# TelTail_Lights_SP_4v1.net
KiCad netlist of a schematic drawn in EAGLE
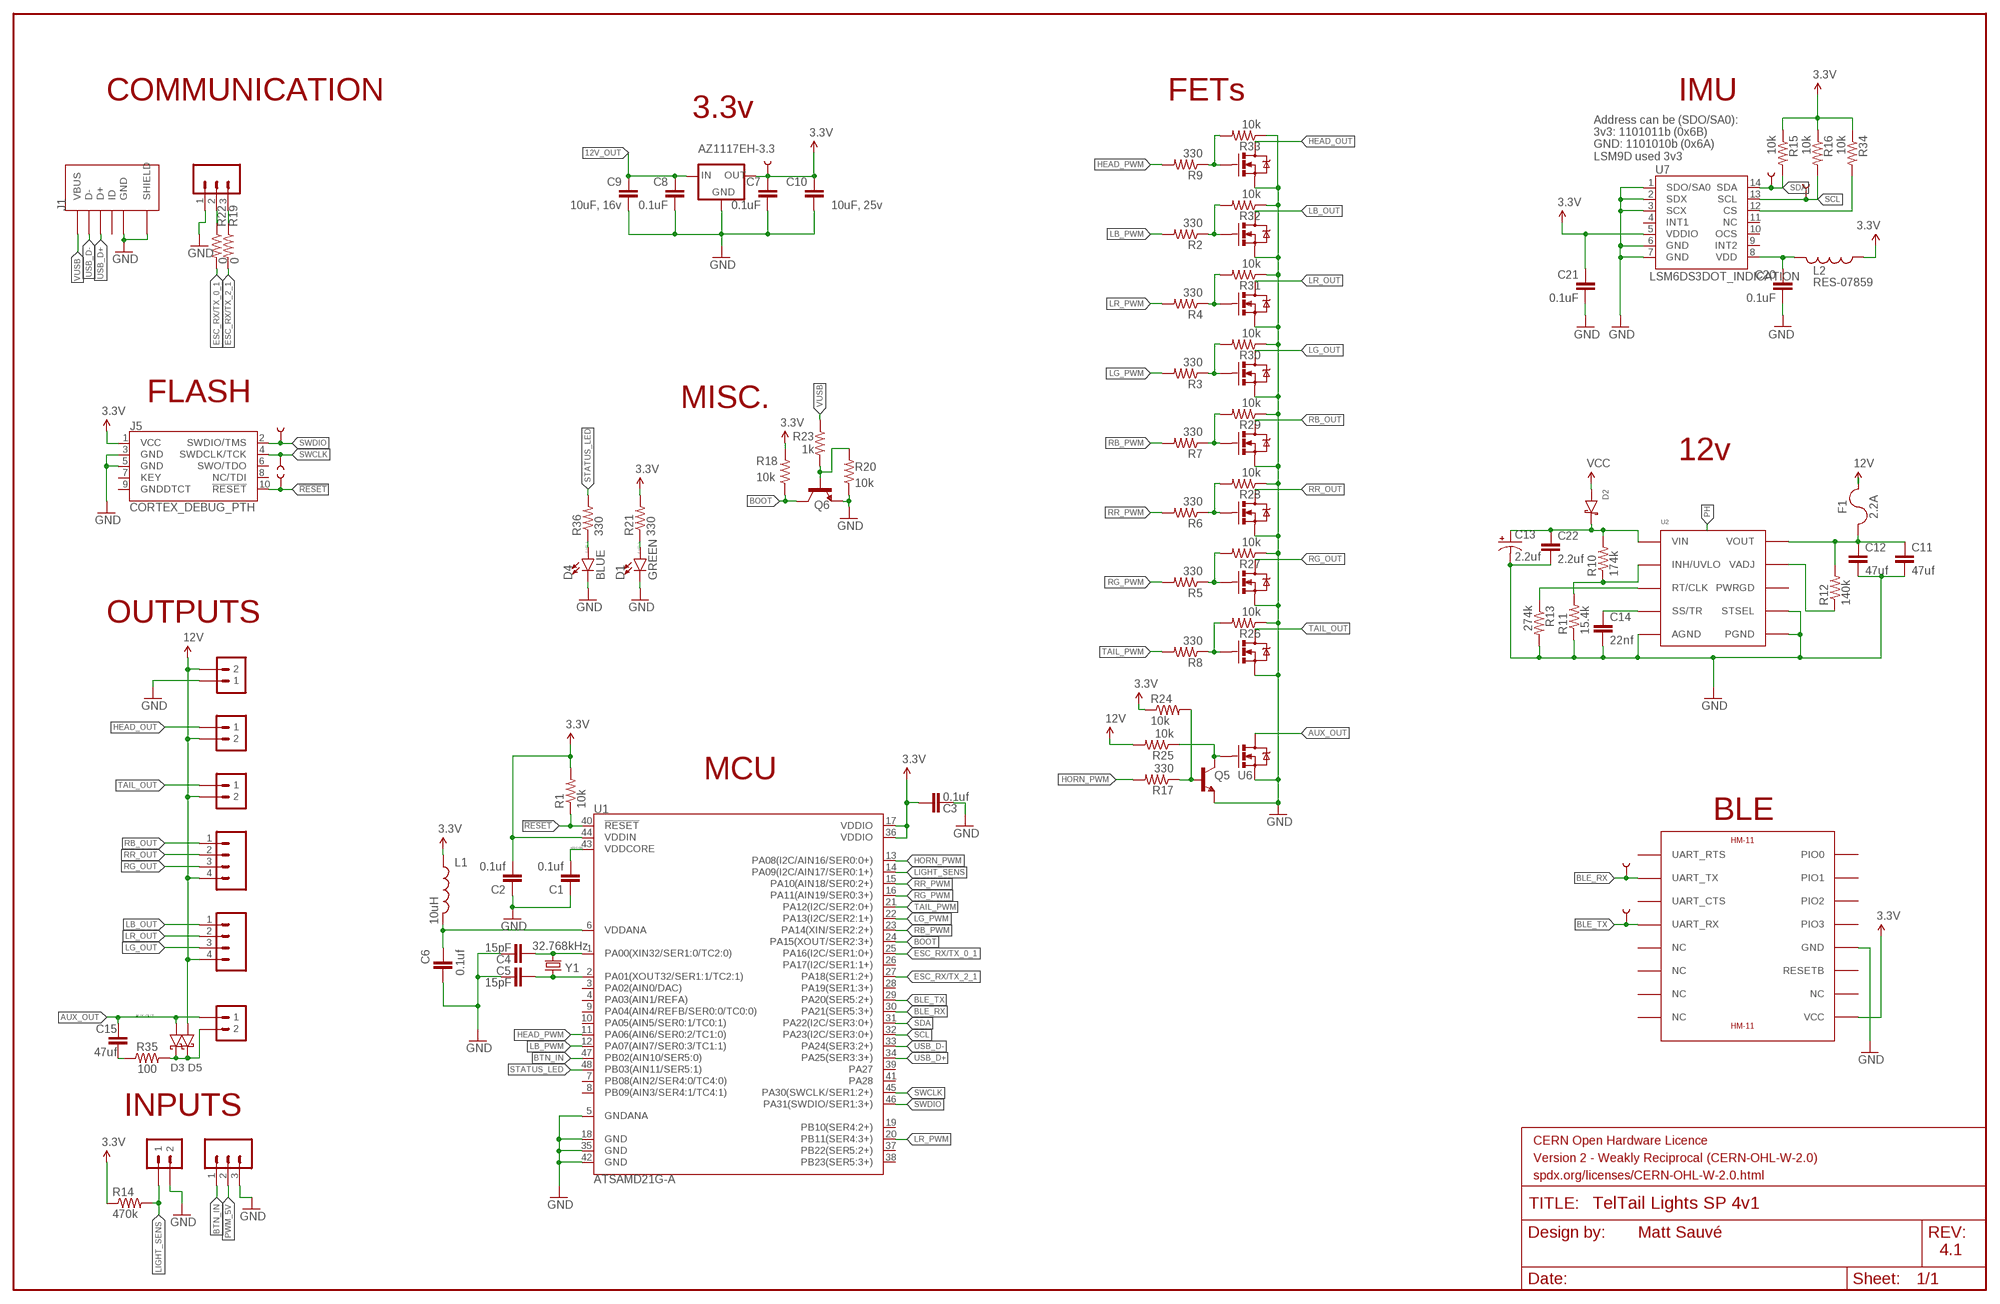
[diagram p0: schematic, sheet 1]

(export (version "E")
  (design (tool "Eeschema 10.0.6"))
  (components
    (comp (ref "C1")
      (value "0.1uf")
      (footprint "eagle-import:0603-CAP")
      (libsource (lib "eagle-import") (part "CAP0603-CAP"))
    )
    (comp (ref "C2")
      (value "0.1uf")
      (footprint "eagle-import:0603-CAP")
      (libsource (lib "eagle-import") (part "CAP0603-CAP"))
    )
    (comp (ref "C3")
      (value "0.1uf")
      (footprint "eagle-import:0603-CAP")
      (libsource (lib "eagle-import") (part "CAP0603-CAP"))
    )
    (comp (ref "C4")
      (value "15pF")
      (footprint "eagle-import:0603-CAP")
      (libsource (lib "eagle-import") (part "CAP0603-CAP"))
    )
    (comp (ref "C5")
      (value "15pF")
      (footprint "eagle-import:0603-CAP")
      (libsource (lib "eagle-import") (part "CAP0603-CAP"))
    )
    (comp (ref "C6")
      (value "0.1uf")
      (footprint "eagle-import:0603-CAP")
      (libsource (lib "eagle-import") (part "CAP0603-CAP"))
    )
    (comp (ref "C7")
      (value "0.1uF")
      (footprint "eagle-import:0603-CAP")
      (libsource (lib "eagle-import") (part "CAP0603-CAP"))
    )
    (comp (ref "C8")
      (value "0.1uF")
      (footprint "eagle-import:0603-CAP")
      (libsource (lib "eagle-import") (part "CAP0603-CAP"))
    )
    (comp (ref "C9")
      (value "10uF, 16v")
      (footprint "eagle-import:0603-CAP")
      (libsource (lib "eagle-import") (part "CAP0603-CAP"))
    )
    (comp (ref "C10")
      (value "10uF, 25v")
      (footprint "eagle-import:0603-CAP")
      (libsource (lib "eagle-import") (part "CAP0603-CAP"))
    )
    (comp (ref "C11")
      (value "47uf")
      (footprint "eagle-import:1210-CAP")
      (libsource (lib "eagle-import") (part "CAP1210"))
    )
    (comp (ref "C12")
      (value "47uf")
      (footprint "eagle-import:1210-CAP")
      (libsource (lib "eagle-import") (part "CAP1210"))
    )
    (comp (ref "C13")
      (value "2.2uf")
      (footprint "eagle-import:PANASONIC_B")
      (libsource (lib "eagle-import") (part "CPOL-USB"))
    )
    (comp (ref "C14")
      (value "22nf")
      (footprint "eagle-import:0402-CAP")
      (libsource (lib "eagle-import") (part "CAP0402-CAP"))
    )
    (comp (ref "C15")
      (value "47uf")
      (footprint "eagle-import:1210-CAP")
      (libsource (lib "eagle-import") (part "CAP1210"))
    )
    (comp (ref "C20")
      (value "0.1uF")
      (footprint "eagle-import:0603-CAP")
      (libsource (lib "eagle-import") (part "CAP0603-CAP"))
    )
    (comp (ref "C21")
      (value "0.1uF")
      (footprint "eagle-import:0603-CAP")
      (libsource (lib "eagle-import") (part "CAP0603-CAP"))
    )
    (comp (ref "C22")
      (value "2.2uf")
      (footprint "eagle-import:1210-CAP")
      (libsource (lib "eagle-import") (part "CAP1210"))
    )
    (comp (ref "D1")
      (value "GREEN")
      (footprint "eagle-import:LED-0603-2")
      (libsource (lib "eagle-import") (part "LED0603"))
    )
    (comp (ref "D2")
      (value "SS210ATR")
      (footprint "eagle-import:DO-214AC")
      (libsource (lib "eagle-import") (part "SS210ATR"))
    )
    (comp (ref "D3")
      (value "PMEG2010ER")
      (footprint "eagle-import:SOD-123W")
      (libsource (lib "eagle-import") (part "PMEG2010ER"))
    )
    (comp (ref "D4")
      (value "BLUE")
      (footprint "eagle-import:LED-0603-2")
      (libsource (lib "eagle-import") (part "LED0603"))
    )
    (comp (ref "D5")
      (value "PMEG2010ER")
      (footprint "eagle-import:SOD-123W")
      (libsource (lib "eagle-import") (part "PMEG2010ER"))
    )
    (comp (ref "F1")
      (value "2.2A")
      (footprint "eagle-import:1206-FUSE")
      (libsource (lib "eagle-import") (part "FUSE-1206"))
    )
    (comp (ref "FRAME2")
      (value "FRAME-LEDGER_CERN_WEAK")
      (footprint "eagle-import:CERN_WEAK")
      (libsource (lib "eagle-import") (part "FRAME-LEDGER_CERN_WEAK"))
    )
    (comp (ref "J1")
      (value "USB3160-XX-XXXX-X-X_REVA")
      (footprint "eagle-import:GCT_USB3160-XX-XXXX-X-X_REVA")
      (fields (field (name "MF") "Global Connector Technology") (field (name "MP") "USB3160-30-0170-0-C"))
      (libsource (lib "eagle-import") (part "USB3160-XX-XXXX-X-X_REVA"))
    )
    (comp (ref "J3")
      (value "JST_PH_3POS")
      (footprint "eagle-import:JST_PH_3POS")
      (libsource (lib "eagle-import") (part "JST_PH_3POS"))
    )
    (comp (ref "J4")
      (value "JST_PH_2POS")
      (footprint "eagle-import:JST_PH_2POS")
      (libsource (lib "eagle-import") (part "JST_PH_2POS"))
    )
    (comp (ref "J5")
      (value "CORTEX_DEBUG_PTH")
      (footprint "eagle-import:2X5-PTH-1.27MM-2")
      (libsource (lib "eagle-import") (part "CORTEX_DEBUG_PTH"))
    )
    (comp (ref "J6")
      (value "JST_PH_2POS")
      (footprint "eagle-import:JST_PH_2POS")
      (libsource (lib "eagle-import") (part "JST_PH_2POS"))
    )
    (comp (ref "J7")
      (value "JST_PH_2POS")
      (footprint "eagle-import:JST_PH_2POS")
      (libsource (lib "eagle-import") (part "JST_PH_2POS"))
    )
    (comp (ref "J8")
      (value "JST_PH_4POS")
      (footprint "eagle-import:JST_PH_4POS")
      (libsource (lib "eagle-import") (part "JST_PH_4POS"))
    )
    (comp (ref "J9")
      (value "JST_PH_4POS")
      (footprint "eagle-import:JST_PH_4POS")
      (libsource (lib "eagle-import") (part "JST_PH_4POS"))
    )
    (comp (ref "J10")
      (value "JST_PH_2POS")
      (footprint "eagle-import:JST_PH_2POS")
      (libsource (lib "eagle-import") (part "JST_PH_2POS"))
    )
    (comp (ref "J11")
      (value "JST_PH_2POS")
      (footprint "eagle-import:JST_PH_2POS")
      (libsource (lib "eagle-import") (part "JST_PH_2POS"))
    )
    (comp (ref "J12")
      (value "JST_PH_3POS")
      (footprint "eagle-import:JST_PH_3POS")
      (libsource (lib "eagle-import") (part "JST_PH_3POS"))
    )
    (comp (ref "L1")
      (value "10uH")
      (footprint "eagle-import:0603-IND")
      (libsource (lib "eagle-import") (part "INDUCTOR0603"))
    )
    (comp (ref "L2")
      (value "RES-07859")
      (footprint "eagle-import:0603-IND")
      (libsource (lib "eagle-import") (part "INDUCTOR0603"))
    )
    (comp (ref "Q1")
      (value "DUAL_NFET_3.5A")
      (footprint "eagle-import:TSOT26")
      (libsource (lib "eagle-import") (part "DUAL_NFET_3.5A"))
    )
    (comp (ref "Q2")
      (value "DUAL_NFET_3.5A")
      (footprint "eagle-import:TSOT26")
      (libsource (lib "eagle-import") (part "DUAL_NFET_3.5A"))
    )
    (comp (ref "Q3")
      (value "DUAL_NFET_3.5A")
      (footprint "eagle-import:TSOT26")
      (libsource (lib "eagle-import") (part "DUAL_NFET_3.5A"))
    )
    (comp (ref "Q4")
      (value "DUAL_NFET_3.5A")
      (footprint "eagle-import:TSOT26")
      (libsource (lib "eagle-import") (part "DUAL_NFET_3.5A"))
    )
    (comp (ref "Q5")
      (value "500mA/300V")
      (footprint "eagle-import:SOT23-3")
      (libsource (lib "eagle-import") (part "TRANS_NPN-MMBTA42"))
    )
    (comp (ref "Q6")
      (value "500mA/300V")
      (footprint "eagle-import:SOT23-3")
      (libsource (lib "eagle-import") (part "TRANS_NPN-MMBTA42"))
    )
    (comp (ref "R1")
      (value "10k")
      (footprint "eagle-import:RES-0402")
      (libsource (lib "eagle-import") (part "RES-0402"))
    )
    (comp (ref "R2")
      (value "330")
      (footprint "eagle-import:RES-0402")
      (libsource (lib "eagle-import") (part "RES-0402"))
    )
    (comp (ref "R3")
      (value "330")
      (footprint "eagle-import:RES-0402")
      (libsource (lib "eagle-import") (part "RES-0402"))
    )
    (comp (ref "R4")
      (value "330")
      (footprint "eagle-import:RES-0402")
      (libsource (lib "eagle-import") (part "RES-0402"))
    )
    (comp (ref "R5")
      (value "330")
      (footprint "eagle-import:RES-0402")
      (libsource (lib "eagle-import") (part "RES-0402"))
    )
    (comp (ref "R6")
      (value "330")
      (footprint "eagle-import:RES-0402")
      (libsource (lib "eagle-import") (part "RES-0402"))
    )
    (comp (ref "R7")
      (value "330")
      (footprint "eagle-import:RES-0402")
      (libsource (lib "eagle-import") (part "RES-0402"))
    )
    (comp (ref "R8")
      (value "330")
      (footprint "eagle-import:RES-0402")
      (libsource (lib "eagle-import") (part "RES-0402"))
    )
    (comp (ref "R9")
      (value "330")
      (footprint "eagle-import:RES-0402")
      (libsource (lib "eagle-import") (part "RES-0402"))
    )
    (comp (ref "R10")
      (value "174k")
      (footprint "eagle-import:RES-0402")
      (libsource (lib "eagle-import") (part "RES-0402"))
    )
    (comp (ref "R11")
      (value "15.4k")
      (footprint "eagle-import:RES-0402")
      (libsource (lib "eagle-import") (part "RES-0402"))
    )
    (comp (ref "R12")
      (value "140k")
      (footprint "eagle-import:RES-0402")
      (libsource (lib "eagle-import") (part "RES-0402"))
    )
    (comp (ref "R13")
      (value "274k")
      (footprint "eagle-import:RES-0402")
      (libsource (lib "eagle-import") (part "RES-0402"))
    )
    (comp (ref "R14")
      (value "470k")
      (footprint "eagle-import:RES-0603")
      (libsource (lib "eagle-import") (part "RES-0603"))
    )
    (comp (ref "R15")
      (value "10k")
      (footprint "eagle-import:RES-0402")
      (libsource (lib "eagle-import") (part "RES-0402"))
    )
    (comp (ref "R16")
      (value "10k")
      (footprint "eagle-import:RES-0402")
      (libsource (lib "eagle-import") (part "RES-0402"))
    )
    (comp (ref "R17")
      (value "330")
      (footprint "eagle-import:RES-0402")
      (libsource (lib "eagle-import") (part "RES-0402"))
    )
    (comp (ref "R18")
      (value "10k")
      (footprint "eagle-import:RES-0402")
      (libsource (lib "eagle-import") (part "RES-0402"))
    )
    (comp (ref "R19")
      (value "0")
      (footprint "eagle-import:RES-0603")
      (libsource (lib "eagle-import") (part "RES-0603"))
    )
    (comp (ref "R20")
      (value "10k")
      (footprint "eagle-import:RES-0402")
      (libsource (lib "eagle-import") (part "RES-0402"))
    )
    (comp (ref "R21")
      (value "330")
      (footprint "eagle-import:RES-0402")
      (libsource (lib "eagle-import") (part "RES-0402"))
    )
    (comp (ref "R22")
      (value "0")
      (footprint "eagle-import:RES-0603")
      (libsource (lib "eagle-import") (part "RES-0603"))
    )
    (comp (ref "R23")
      (value "1k")
      (footprint "eagle-import:RES-0402")
      (libsource (lib "eagle-import") (part "RES-0402"))
    )
    (comp (ref "R24")
      (value "10k")
      (footprint "eagle-import:RES-0402")
      (libsource (lib "eagle-import") (part "RES-0402"))
    )
    (comp (ref "R25")
      (value "10k")
      (footprint "eagle-import:RES-0402")
      (libsource (lib "eagle-import") (part "RES-0402"))
    )
    (comp (ref "R26")
      (value "10k")
      (footprint "eagle-import:RES-0402")
      (libsource (lib "eagle-import") (part "RES-0402"))
    )
    (comp (ref "R27")
      (value "10k")
      (footprint "eagle-import:RES-0402")
      (libsource (lib "eagle-import") (part "RES-0402"))
    )
    (comp (ref "R28")
      (value "10k")
      (footprint "eagle-import:RES-0402")
      (libsource (lib "eagle-import") (part "RES-0402"))
    )
    (comp (ref "R29")
      (value "10k")
      (footprint "eagle-import:RES-0402")
      (libsource (lib "eagle-import") (part "RES-0402"))
    )
    (comp (ref "R30")
      (value "10k")
      (footprint "eagle-import:RES-0402")
      (libsource (lib "eagle-import") (part "RES-0402"))
    )
    (comp (ref "R31")
      (value "10k")
      (footprint "eagle-import:RES-0402")
      (libsource (lib "eagle-import") (part "RES-0402"))
    )
    (comp (ref "R32")
      (value "10k")
      (footprint "eagle-import:RES-0402")
      (libsource (lib "eagle-import") (part "RES-0402"))
    )
    (comp (ref "R33")
      (value "10k")
      (footprint "eagle-import:RES-0402")
      (libsource (lib "eagle-import") (part "RES-0402"))
    )
    (comp (ref "R34")
      (value "10k")
      (footprint "eagle-import:RES-0402")
      (libsource (lib "eagle-import") (part "RES-0402"))
    )
    (comp (ref "R35")
      (value "100")
      (footprint "eagle-import:0805-RES")
      (libsource (lib "eagle-import") (part "RESISTOR0805"))
    )
    (comp (ref "R36")
      (value "330")
      (footprint "eagle-import:RES-0402")
      (libsource (lib "eagle-import") (part "RES-0402"))
    )
    (comp (ref "TP1")
      (value "1MM_TP")
      (footprint "eagle-import:1MM_TP")
      (libsource (lib "eagle-import") (part "1MM_TP"))
    )
    (comp (ref "TP2")
      (value "1MM_TP")
      (footprint "eagle-import:1MM_TP")
      (libsource (lib "eagle-import") (part "1MM_TP"))
    )
    (comp (ref "TP3")
      (value "1MM_TP")
      (footprint "eagle-import:1MM_TP")
      (libsource (lib "eagle-import") (part "1MM_TP"))
    )
    (comp (ref "TP4")
      (value "1MM_TP")
      (footprint "eagle-import:1MM_TP")
      (libsource (lib "eagle-import") (part "1MM_TP"))
    )
    (comp (ref "TP5")
      (value "1MM_TP")
      (footprint "eagle-import:1MM_TP")
      (libsource (lib "eagle-import") (part "1MM_TP"))
    )
    (comp (ref "TP8")
      (value "1MM_TP")
      (footprint "eagle-import:1MM_TP")
      (libsource (lib "eagle-import") (part "1MM_TP"))
    )
    (comp (ref "TP9")
      (value "1MM_TP")
      (footprint "eagle-import:1MM_TP")
      (libsource (lib "eagle-import") (part "1MM_TP"))
    )
    (comp (ref "TP10")
      (value "1MM_TP")
      (footprint "eagle-import:1MM_TP")
      (libsource (lib "eagle-import") (part "1MM_TP"))
    )
    (comp (ref "U1")
      (value "ATSAMD21G-A")
      (footprint "eagle-import:TQFP-48")
      (libsource (lib "eagle-import") (part "ATSAMD21G-A"))
    )
    (comp (ref "U2")
      (value "LMZ35003")
      (footprint "eagle-import:41-BQFN")
      (libsource (lib "eagle-import") (part "LMZ35003"))
    )
    (comp (ref "U3")
      (value "HM-11")
      (footprint "eagle-import:HM-11")
      (libsource (lib "eagle-import") (part "HM-11"))
    )
    (comp (ref "U4")
      (value "AZ1117EH-3.3")
      (footprint "eagle-import:SOT-223")
      (libsource (lib "eagle-import") (part "AZ1117EH-3.3"))
    )
    (comp (ref "U6")
      (value "PSMN8R5-60YS")
      (footprint "eagle-import:SOT669")
      (libsource (lib "eagle-import") (part "PSMN8R5-60YS"))
    )
    (comp (ref "U7")
      (value "LSM6DS3DOT_INDICATION")
      (footprint "eagle-import:LGA14L_DOT_INDICATOR")
      (libsource (lib "eagle-import") (part "LSM6DS3DOT_INDICATION"))
    )
    (comp (ref "Y1")
      (value "32.768kHz")
      (footprint "eagle-import:CRYSTAL-SMD-3.2X1.5MM")
      (libsource (lib "eagle-import") (part "CRYSTAL-32.768KHZSMD-3.2X1.5"))
    )
  )
  (nets
    (net (code "1") (name "/P_LED_0") (class "Default")
      (node (ref "D1") (pin "A") (pinfunction "A_A") (pintype "passive"))
      (node (ref "R21") (pin "1") (pinfunction "1_1") (pintype "passive"))
    )
    (net (code "2") (name "/S_LED_0") (class "Default")
      (node (ref "D4") (pin "A") (pinfunction "A_A") (pintype "passive"))
      (node (ref "R36") (pin "1") (pinfunction "1_1") (pintype "passive"))
    )
    (net (code "3") (name "/VDDCORE") (class "Default")
      (node (ref "C1") (pin "2") (pinfunction "2_2") (pintype "passive"))
      (node (ref "U1") (pin "43") (pinfunction "VDDCORE_43") (pintype "bidirectional"))
    )
    (net (code "4") (name "/~{RESET}") (class "Default")
      (node (ref "J5") (pin "10") (pinfunction "~{RESET}_10") (pintype "bidirectional"))
      (node (ref "R1") (pin "1") (pinfunction "1_1") (pintype "passive"))
      (node (ref "TP10") (pin "P$1") (pinfunction "1_P$1") (pintype "bidirectional"))
      (node (ref "U1") (pin "40") (pinfunction "~{RESET}_40") (pintype "bidirectional"))
    )
    (net (code "5") (name "3.3V") (class "Default")
      (node (ref "C10") (pin "1") (pinfunction "1_1") (pintype "passive"))
      (node (ref "C2") (pin "2") (pinfunction "2_2") (pintype "passive"))
      (node (ref "C21") (pin "1") (pinfunction "1_1") (pintype "passive"))
      (node (ref "C3") (pin "2") (pinfunction "2_2") (pintype "passive"))
      (node (ref "C7") (pin "1") (pinfunction "1_1") (pintype "passive"))
      (node (ref "J5") (pin "1") (pinfunction "VCC_1") (pintype "bidirectional"))
      (node (ref "L1") (pin "1") (pinfunction "1_1") (pintype "passive"))
      (node (ref "L2") (pin "1") (pinfunction "1_1") (pintype "passive"))
      (node (ref "R1") (pin "2") (pinfunction "2_2") (pintype "passive"))
      (node (ref "R14") (pin "1") (pinfunction "1_1") (pintype "passive"))
      (node (ref "R15") (pin "1") (pinfunction "1_1") (pintype "passive"))
      (node (ref "R16") (pin "1") (pinfunction "1_1") (pintype "passive"))
      (node (ref "R18") (pin "2") (pinfunction "2_2") (pintype "passive"))
      (node (ref "R21") (pin "2") (pinfunction "2_2") (pintype "passive"))
      (node (ref "R24") (pin "1") (pinfunction "1_1") (pintype "passive"))
      (node (ref "R34") (pin "1") (pinfunction "1_1") (pintype "passive"))
      (node (ref "TP3") (pin "P$1") (pinfunction "1_P$1") (pintype "bidirectional"))
      (node (ref "U1") (pin "17") (pinfunction "VDDIO_17") (pintype "bidirectional"))
      (node (ref "U1") (pin "36") (pinfunction "VDDIO_36") (pintype "bidirectional"))
      (node (ref "U1") (pin "44") (pinfunction "VDDIN_44") (pintype "bidirectional"))
      (node (ref "U3") (pin "VCC") (pinfunction "VCC_VCC") (pintype "bidirectional"))
      (node (ref "U4") (pin "2") (pinfunction "OUT_2") (pintype "passive"))
      (node (ref "U4") (pin "4") (pinfunction "OUT_4") (pintype "passive"))
      (node (ref "U7") (pin "5") (pinfunction "VDDIO_5") (pintype "bidirectional"))
    )
    (net (code "6") (name "12V") (class "Default")
      (node (ref "D5") (pin "2") (pinfunction "ANODE_2") (pintype "bidirectional"))
      (node (ref "F1") (pin "2") (pinfunction "2_2") (pintype "bidirectional"))
      (node (ref "J4") (pin "2") (pinfunction "2_2") (pintype "passive"))
      (node (ref "J6") (pin "2") (pinfunction "2_2") (pintype "passive"))
      (node (ref "J7") (pin "2") (pinfunction "2_2") (pintype "passive"))
      (node (ref "J8") (pin "4") (pinfunction "4_4") (pintype "passive"))
      (node (ref "J9") (pin "4") (pinfunction "4_4") (pintype "passive"))
      (node (ref "R25") (pin "2") (pinfunction "2_2") (pintype "passive"))
    )
    (net (code "7") (name "12V_OUT") (class "Default")
      (node (ref "C11") (pin "1") (pinfunction "1_1") (pintype "passive"))
      (node (ref "C12") (pin "1") (pinfunction "1_1") (pintype "passive"))
      (node (ref "C8") (pin "1") (pinfunction "1_1") (pintype "passive"))
      (node (ref "C9") (pin "1") (pinfunction "1_1") (pintype "passive"))
      (node (ref "F1") (pin "1") (pinfunction "1_1") (pintype "bidirectional"))
      (node (ref "R12") (pin "2") (pinfunction "2_2") (pintype "passive"))
      (node (ref "U2") (pin "P$10") (pinfunction "VOUT_P$10") (pintype "bidirectional"))
      (node (ref "U2") (pin "P$11") (pinfunction "VOUT_P$11") (pintype "bidirectional"))
      (node (ref "U2") (pin "P$12") (pinfunction "VOUT_P$12") (pintype "bidirectional"))
      (node (ref "U2") (pin "P$13") (pinfunction "VOUT_P$13") (pintype "bidirectional"))
      (node (ref "U2") (pin "P$14") (pinfunction "VOUT_P$14") (pintype "bidirectional"))
      (node (ref "U2") (pin "P$15") (pinfunction "VOUT_P$15") (pintype "bidirectional"))
      (node (ref "U2") (pin "VOUT") (pinfunction "VOUT_VOUT") (pintype "bidirectional"))
      (node (ref "U4") (pin "3") (pinfunction "IN_3") (pintype "input"))
    )
    (net (code "8") (name "AUX_OUT") (class "Default")
      (node (ref "C15") (pin "1") (pinfunction "1_1") (pintype "passive"))
      (node (ref "D3") (pin "2") (pinfunction "ANODE_2") (pintype "bidirectional"))
      (node (ref "J10") (pin "1") (pinfunction "1_1") (pintype "passive"))
      (node (ref "U6") (pin "P$1") (pinfunction "D_P$1") (pintype "passive"))
      (node (ref "U6") (pin "P$2") (pinfunction "D_P$2") (pintype "passive"))
    )
    (net (code "9") (name "BLE_RX") (class "Default")
      (node (ref "TP2") (pin "P$1") (pinfunction "1_P$1") (pintype "bidirectional"))
      (node (ref "U1") (pin "30") (pinfunction "PA21(SER5:3+)_30") (pintype "bidirectional"))
      (node (ref "U3") (pin "UART_TX") (pinfunction "UART_TX_UART_TX") (pintype "bidirectional"))
    )
    (net (code "10") (name "BLE_TX") (class "Default")
      (node (ref "TP1") (pin "P$1") (pinfunction "1_P$1") (pintype "bidirectional"))
      (node (ref "U1") (pin "29") (pinfunction "PA20(SER5:2+)_29") (pintype "bidirectional"))
      (node (ref "U3") (pin "UART_RX") (pinfunction "UART_RX_UART_RX") (pintype "bidirectional"))
    )
    (net (code "11") (name "BOOT") (class "Default")
      (node (ref "Q6") (pin "3") (pinfunction "C_3") (pintype "passive"))
      (node (ref "R18") (pin "1") (pinfunction "1_1") (pintype "passive"))
      (node (ref "U1") (pin "24") (pinfunction "PA15(XOUT/SER2:3+)_24") (pintype "bidirectional"))
    )
    (net (code "12") (name "BTN_IN") (class "Default")
      (node (ref "J12") (pin "1") (pinfunction "2_1") (pintype "passive"))
      (node (ref "U1") (pin "47") (pinfunction "PB02(AIN10/SER5:0)_47") (pintype "bidirectional"))
    )
    (net (code "13") (name "ESC_RX{slash}TX_0_1") (class "Default")
      (node (ref "R22") (pin "2") (pinfunction "2_2") (pintype "passive"))
      (node (ref "U1") (pin "25") (pinfunction "PA16(I2C/SER1:0+)_25") (pintype "bidirectional"))
    )
    (net (code "14") (name "ESC_RX{slash}TX_2_1") (class "Default")
      (node (ref "R19") (pin "2") (pinfunction "2_2") (pintype "passive"))
      (node (ref "U1") (pin "27") (pinfunction "PA18(SER1:2+)_27") (pintype "bidirectional"))
    )
    (net (code "15") (name "GND") (class "Default")
      (node (ref "C1") (pin "1") (pinfunction "1_1") (pintype "passive"))
      (node (ref "C10") (pin "2") (pinfunction "2_2") (pintype "passive"))
      (node (ref "C11") (pin "2") (pinfunction "2_2") (pintype "passive"))
      (node (ref "C12") (pin "2") (pinfunction "2_2") (pintype "passive"))
      (node (ref "C13") (pin "-") (pinfunction "-_-") (pintype "passive"))
      (node (ref "C14") (pin "2") (pinfunction "2_2") (pintype "passive"))
      (node (ref "C2") (pin "1") (pinfunction "1_1") (pintype "passive"))
      (node (ref "C20") (pin "2") (pinfunction "2_2") (pintype "passive"))
      (node (ref "C21") (pin "2") (pinfunction "2_2") (pintype "passive"))
      (node (ref "C22") (pin "2") (pinfunction "2_2") (pintype "passive"))
      (node (ref "C3") (pin "1") (pinfunction "1_1") (pintype "passive"))
      (node (ref "C4") (pin "2") (pinfunction "2_2") (pintype "passive"))
      (node (ref "C5") (pin "2") (pinfunction "2_2") (pintype "passive"))
      (node (ref "C6") (pin "2") (pinfunction "2_2") (pintype "passive"))
      (node (ref "C7") (pin "2") (pinfunction "2_2") (pintype "passive"))
      (node (ref "C8") (pin "2") (pinfunction "2_2") (pintype "passive"))
      (node (ref "C9") (pin "2") (pinfunction "2_2") (pintype "passive"))
      (node (ref "D1") (pin "C") (pinfunction "C_C") (pintype "passive"))
      (node (ref "D4") (pin "C") (pinfunction "C_C") (pintype "passive"))
      (node (ref "J1") (pin "5") (pinfunction "GND_5") (pintype "power_in"))
      (node (ref "J1") (pin "6") (pinfunction "SHIELD_6") (pintype "passive"))
      (node (ref "J1") (pin "7") (pinfunction "SHIELD_7") (pintype "passive"))
      (node (ref "J1") (pin "8") (pinfunction "SHIELD_8") (pintype "passive"))
      (node (ref "J11") (pin "2") (pinfunction "2_2") (pintype "passive"))
      (node (ref "J12") (pin "3") (pinfunction "4_3") (pintype "passive"))
      (node (ref "J3") (pin "1") (pinfunction "2_1") (pintype "passive"))
      (node (ref "J4") (pin "1") (pinfunction "1_1") (pintype "passive"))
      (node (ref "J5") (pin "3") (pinfunction "GND_3") (pintype "bidirectional"))
      (node (ref "J5") (pin "5") (pinfunction "GND_5") (pintype "bidirectional"))
      (node (ref "Q1") (pin "2") (pinfunction "S_2") (pintype "passive"))
      (node (ref "Q1") (pin "5") (pinfunction "S_5") (pintype "passive"))
      (node (ref "Q2") (pin "2") (pinfunction "S_2") (pintype "passive"))
      (node (ref "Q2") (pin "5") (pinfunction "S_5") (pintype "passive"))
      (node (ref "Q3") (pin "2") (pinfunction "S_2") (pintype "passive"))
      (node (ref "Q3") (pin "5") (pinfunction "S_5") (pintype "passive"))
      (node (ref "Q4") (pin "2") (pinfunction "S_2") (pintype "passive"))
      (node (ref "Q4") (pin "5") (pinfunction "S_5") (pintype "passive"))
      (node (ref "Q5") (pin "2") (pinfunction "E_2") (pintype "passive"))
      (node (ref "Q6") (pin "2") (pinfunction "E_2") (pintype "passive"))
      (node (ref "R11") (pin "1") (pinfunction "1_1") (pintype "passive"))
      (node (ref "R13") (pin "2") (pinfunction "2_2") (pintype "passive"))
      (node (ref "R20") (pin "1") (pinfunction "1_1") (pintype "passive"))
      (node (ref "R26") (pin "1") (pinfunction "1_1") (pintype "passive"))
      (node (ref "R27") (pin "1") (pinfunction "1_1") (pintype "passive"))
      (node (ref "R28") (pin "1") (pinfunction "1_1") (pintype "passive"))
      (node (ref "R29") (pin "1") (pinfunction "1_1") (pintype "passive"))
      (node (ref "R30") (pin "1") (pinfunction "1_1") (pintype "passive"))
      (node (ref "R31") (pin "1") (pinfunction "1_1") (pintype "passive"))
      (node (ref "R32") (pin "1") (pinfunction "1_1") (pintype "passive"))
      (node (ref "R33") (pin "1") (pinfunction "1_1") (pintype "passive"))
      (node (ref "U1") (pin "18") (pinfunction "GND_18") (pintype "bidirectional"))
      (node (ref "U1") (pin "35") (pinfunction "GND_35") (pintype "bidirectional"))
      (node (ref "U1") (pin "42") (pinfunction "GND_42") (pintype "bidirectional"))
      (node (ref "U1") (pin "5") (pinfunction "GNDANA_5") (pintype "bidirectional"))
      (node (ref "U2") (pin "AGND") (pinfunction "AGND_AGND") (pintype "bidirectional"))
      (node (ref "U2") (pin "P$1") (pinfunction "AGND_P$1") (pintype "bidirectional"))
      (node (ref "U2") (pin "P$16") (pinfunction "PGND_P$16") (pintype "bidirectional"))
      (node (ref "U2") (pin "P$17") (pinfunction "PGND_P$17") (pintype "bidirectional"))
      (node (ref "U2") (pin "P$18") (pinfunction "PGND_P$18") (pintype "bidirectional"))
      (node (ref "U2") (pin "P$19") (pinfunction "PGND_P$19") (pintype "bidirectional"))
      (node (ref "U2") (pin "P$20") (pinfunction "PGND_P$20") (pintype "bidirectional"))
      (node (ref "U2") (pin "P$29") (pinfunction "STSEL_P$29") (pintype "bidirectional"))
      (node (ref "U2") (pin "P$30") (pinfunction "AGND_P$30") (pintype "bidirectional"))
      (node (ref "U2") (pin "P$32") (pinfunction "AGND_P$32") (pintype "bidirectional"))
      (node (ref "U2") (pin "P$33") (pinfunction "AGND_P$33") (pintype "bidirectional"))
      (node (ref "U2") (pin "P$34") (pinfunction "AGND_P$34") (pintype "bidirectional"))
      (node (ref "U2") (pin "P$4") (pinfunction "AGND_P$4") (pintype "bidirectional"))
      (node (ref "U2") (pin "P$5") (pinfunction "AGND_P$5") (pintype "bidirectional"))
      (node (ref "U2") (pin "P$8") (pinfunction "AGND_P$8") (pintype "bidirectional"))
      (node (ref "U2") (pin "P$9") (pinfunction "AGND_P$9") (pintype "bidirectional"))
      (node (ref "U2") (pin "PGND1") (pinfunction "PGND_PGND1") (pintype "bidirectional"))
      (node (ref "U3") (pin "GND") (pinfunction "GND_GND") (pintype "bidirectional"))
      (node (ref "U4") (pin "1") (pinfunction "GND_1") (pintype "input"))
      (node (ref "U6") (pin "1") (pinfunction "S_1") (pintype "passive"))
      (node (ref "U6") (pin "2") (pinfunction "S_2") (pintype "passive"))
      (node (ref "U6") (pin "3") (pinfunction "S_3") (pintype "passive"))
      (node (ref "U7") (pin "1") (pinfunction "SDO/SA0_1") (pintype "bidirectional"))
      (node (ref "U7") (pin "2") (pinfunction "SDX_2") (pintype "bidirectional"))
      (node (ref "U7") (pin "3") (pinfunction "SCX_3") (pintype "bidirectional"))
      (node (ref "U7") (pin "6") (pinfunction "GND_6") (pintype "bidirectional"))
      (node (ref "U7") (pin "7") (pinfunction "GND_7") (pintype "bidirectional"))
    )
    (net (code "16") (name "HEAD_OUT") (class "Default")
      (node (ref "J6") (pin "1") (pinfunction "1_1") (pintype "passive"))
      (node (ref "Q1") (pin "4") (pinfunction "D_4") (pintype "passive"))
    )
    (net (code "17") (name "HEAD_PWM") (class "Default")
      (node (ref "R9") (pin "2") (pinfunction "2_2") (pintype "passive"))
      (node (ref "U1") (pin "11") (pinfunction "PA06(AIN6/SER0:2/TC1:0)_11") (pintype "bidirectional"))
    )
    (net (code "18") (name "HORN_PWM") (class "Default")
      (node (ref "R17") (pin "2") (pinfunction "2_2") (pintype "passive"))
      (node (ref "U1") (pin "13") (pinfunction "PA08(I2C/AIN16/SER0:0+)_13") (pintype "bidirectional"))
    )
    (net (code "19") (name "LB_OUT") (class "Default")
      (node (ref "J9") (pin "1") (pinfunction "1_1") (pintype "passive"))
      (node (ref "Q1") (pin "6") (pinfunction "D_6") (pintype "passive"))
    )
    (net (code "20") (name "LB_PWM") (class "Default")
      (node (ref "R2") (pin "2") (pinfunction "2_2") (pintype "passive"))
      (node (ref "U1") (pin "12") (pinfunction "PA07(AIN7/SER0:3/TC1:1)_12") (pintype "bidirectional"))
    )
    (net (code "21") (name "LG_OUT") (class "Default")
      (node (ref "J9") (pin "3") (pinfunction "3_3") (pintype "passive"))
      (node (ref "Q2") (pin "6") (pinfunction "D_6") (pintype "passive"))
    )
    (net (code "22") (name "LG_PWM") (class "Default")
      (node (ref "R3") (pin "2") (pinfunction "2_2") (pintype "passive"))
      (node (ref "U1") (pin "22") (pinfunction "PA13(I2C/SER2:1+)_22") (pintype "bidirectional"))
    )
    (net (code "23") (name "LIGHT_SENS") (class "Default")
      (node (ref "J11") (pin "1") (pinfunction "1_1") (pintype "passive"))
      (node (ref "R14") (pin "2") (pinfunction "2_2") (pintype "passive"))
      (node (ref "U1") (pin "14") (pinfunction "PA09(I2C/AIN17/SER0:1+)_14") (pintype "bidirectional"))
    )
    (net (code "24") (name "LR_OUT") (class "Default")
      (node (ref "J9") (pin "2") (pinfunction "2_2") (pintype "passive"))
      (node (ref "Q2") (pin "4") (pinfunction "D_4") (pintype "passive"))
    )
    (net (code "25") (name "LR_PWM") (class "Default")
      (node (ref "R4") (pin "2") (pinfunction "2_2") (pintype "passive"))
      (node (ref "U1") (pin "20") (pinfunction "PB11(SER4:3+)_20") (pintype "bidirectional"))
    )
    (net (code "26") (name "Net-(C15-Pad2)") (class "Default")
      (node (ref "C15") (pin "2") (pinfunction "2_2") (pintype "passive"))
      (node (ref "R35") (pin "1") (pinfunction "1_1") (pintype "passive"))
    )
    (net (code "27") (name "Net-(D3-CATHODE)") (class "Default")
      (node (ref "D3") (pin "1") (pinfunction "CATHODE_1") (pintype "bidirectional"))
      (node (ref "D5") (pin "1") (pinfunction "CATHODE_1") (pintype "bidirectional"))
      (node (ref "J10") (pin "2") (pinfunction "2_2") (pintype "passive"))
      (node (ref "R35") (pin "2") (pinfunction "2_2") (pintype "passive"))
    )
    (net (code "28") (name "Net-(J3-3)") (class "Default")
      (node (ref "J3") (pin "2") (pinfunction "3_2") (pintype "passive"))
      (node (ref "R22") (pin "1") (pinfunction "1_1") (pintype "passive"))
    )
    (net (code "29") (name "Net-(J3-4)") (class "Default")
      (node (ref "J3") (pin "3") (pinfunction "4_3") (pintype "passive"))
      (node (ref "R19") (pin "1") (pinfunction "1_1") (pintype "passive"))
    )
    (net (code "30") (name "Net-(Q1A-G)") (class "Default")
      (node (ref "Q1") (pin "1") (pinfunction "G_1") (pintype "passive"))
      (node (ref "R2") (pin "1") (pinfunction "1_1") (pintype "passive"))
      (node (ref "R32") (pin "2") (pinfunction "2_2") (pintype "passive"))
    )
    (net (code "31") (name "Net-(Q1B-G)") (class "Default")
      (node (ref "Q1") (pin "3") (pinfunction "G_3") (pintype "passive"))
      (node (ref "R33") (pin "2") (pinfunction "2_2") (pintype "passive"))
      (node (ref "R9") (pin "1") (pinfunction "1_1") (pintype "passive"))
    )
    (net (code "32") (name "Net-(Q2A-G)") (class "Default")
      (node (ref "Q2") (pin "1") (pinfunction "G_1") (pintype "passive"))
      (node (ref "R3") (pin "1") (pinfunction "1_1") (pintype "passive"))
      (node (ref "R30") (pin "2") (pinfunction "2_2") (pintype "passive"))
    )
    (net (code "33") (name "Net-(Q2B-G)") (class "Default")
      (node (ref "Q2") (pin "3") (pinfunction "G_3") (pintype "passive"))
      (node (ref "R31") (pin "2") (pinfunction "2_2") (pintype "passive"))
      (node (ref "R4") (pin "1") (pinfunction "1_1") (pintype "passive"))
    )
    (net (code "34") (name "Net-(Q3A-G)") (class "Default")
      (node (ref "Q3") (pin "1") (pinfunction "G_1") (pintype "passive"))
      (node (ref "R28") (pin "2") (pinfunction "2_2") (pintype "passive"))
      (node (ref "R6") (pin "1") (pinfunction "1_1") (pintype "passive"))
    )
    (net (code "35") (name "Net-(Q3B-G)") (class "Default")
      (node (ref "Q3") (pin "3") (pinfunction "G_3") (pintype "passive"))
      (node (ref "R29") (pin "2") (pinfunction "2_2") (pintype "passive"))
      (node (ref "R7") (pin "1") (pinfunction "1_1") (pintype "passive"))
    )
    (net (code "36") (name "Net-(Q4A-G)") (class "Default")
      (node (ref "Q4") (pin "1") (pinfunction "G_1") (pintype "passive"))
      (node (ref "R26") (pin "2") (pinfunction "2_2") (pintype "passive"))
      (node (ref "R8") (pin "1") (pinfunction "1_1") (pintype "passive"))
    )
    (net (code "37") (name "Net-(Q4B-G)") (class "Default")
      (node (ref "Q4") (pin "3") (pinfunction "G_3") (pintype "passive"))
      (node (ref "R27") (pin "2") (pinfunction "2_2") (pintype "passive"))
      (node (ref "R5") (pin "1") (pinfunction "1_1") (pintype "passive"))
    )
    (net (code "38") (name "Net-(Q5-B)") (class "Default")
      (node (ref "Q5") (pin "1") (pinfunction "B_1") (pintype "passive"))
      (node (ref "R17") (pin "1") (pinfunction "1_1") (pintype "passive"))
      (node (ref "R24") (pin "2") (pinfunction "2_2") (pintype "passive"))
    )
    (net (code "39") (name "Net-(Q5-C)") (class "Default")
      (node (ref "Q5") (pin "3") (pinfunction "C_3") (pintype "passive"))
      (node (ref "R25") (pin "1") (pinfunction "1_1") (pintype "passive"))
      (node (ref "U6") (pin "4") (pinfunction "G_4") (pintype "passive"))
    )
    (net (code "40") (name "Net-(Q6-B)") (class "Default")
      (node (ref "Q6") (pin "1") (pinfunction "B_1") (pintype "passive"))
      (node (ref "R20") (pin "2") (pinfunction "2_2") (pintype "passive"))
      (node (ref "R23") (pin "2") (pinfunction "2_2") (pintype "passive"))
    )
    (net (code "41") (name "Net-(U1-PA00(XIN32{slash}SER1:0{slash}TC2:0))") (class "Default")
      (node (ref "C4") (pin "1") (pinfunction "1_1") (pintype "passive"))
      (node (ref "U1") (pin "1") (pinfunction "PA00(XIN32/SER1:0/TC2:0)_1") (pintype "bidirectional"))
      (node (ref "Y1") (pin "P$2") (pinfunction "2_P$2") (pintype "passive"))
    )
    (net (code "42") (name "Net-(U1-PA01(XOUT32{slash}SER1:1{slash}TC2:1))") (class "Default")
      (node (ref "C5") (pin "1") (pinfunction "1_1") (pintype "passive"))
      (node (ref "U1") (pin "2") (pinfunction "PA01(XOUT32/SER1:1/TC2:1)_2") (pintype "bidirectional"))
      (node (ref "Y1") (pin "P$1") (pinfunction "1_P$1") (pintype "passive"))
    )
    (net (code "43") (name "Net-(U1-VDDANA)") (class "Default")
      (node (ref "C6") (pin "1") (pinfunction "1_1") (pintype "passive"))
      (node (ref "L1") (pin "2") (pinfunction "2_2") (pintype "passive"))
      (node (ref "U1") (pin "6") (pinfunction "VDDANA_6") (pintype "bidirectional"))
    )
    (net (code "44") (name "Net-(U2-INH{slash}UVLO)") (class "Default")
      (node (ref "R10") (pin "1") (pinfunction "1_1") (pintype "passive"))
      (node (ref "R11") (pin "2") (pinfunction "2_2") (pintype "passive"))
      (node (ref "U2") (pin "P$27") (pinfunction "INH/UVLO_P$27") (pintype "bidirectional"))
    )
    (net (code "45") (name "Net-(U2-RT{slash}CLK)") (class "Default")
      (node (ref "R13") (pin "1") (pinfunction "1_1") (pintype "passive"))
      (node (ref "U2") (pin "P$31") (pinfunction "RT/CLK_P$31") (pintype "bidirectional"))
    )
    (net (code "46") (name "Net-(U2-SS{slash}TR)") (class "Default")
      (node (ref "C14") (pin "1") (pinfunction "1_1") (pintype "passive"))
      (node (ref "U2") (pin "P$28") (pinfunction "SS/TR_P$28") (pintype "bidirectional"))
    )
    (net (code "47") (name "Net-(U2-VADJ)") (class "Default")
      (node (ref "R12") (pin "1") (pinfunction "1_1") (pintype "passive"))
      (node (ref "U2") (pin "P$36") (pinfunction "VADJ_P$36") (pintype "bidirectional"))
    )
    (net (code "48") (name "Net-(U2-VIN)") (class "Default")
      (node (ref "C13") (pin "+") (pinfunction "+_+") (pintype "passive"))
      (node (ref "C22") (pin "1") (pinfunction "1_1") (pintype "passive"))
      (node (ref "D2") (pin "CATHODE") (pinfunction "CATHODE_CATHODE") (pintype "bidirectional"))
      (node (ref "R10") (pin "2") (pinfunction "2_2") (pintype "passive"))
      (node (ref "U2") (pin "P$26") (pinfunction "VIN_P$26") (pintype "bidirectional"))
    )
    (net (code "49") (name "Net-(U7-CS)") (class "Default")
      (node (ref "R34") (pin "2") (pinfunction "2_2") (pintype "passive"))
      (node (ref "U7") (pin "12") (pinfunction "CS_12") (pintype "bidirectional"))
    )
    (net (code "50") (name "Net-(U7-VDD)") (class "Default")
      (node (ref "C20") (pin "1") (pinfunction "1_1") (pintype "passive"))
      (node (ref "L2") (pin "2") (pinfunction "2_2") (pintype "passive"))
      (node (ref "U7") (pin "8") (pinfunction "VDD_8") (pintype "bidirectional"))
    )
    (net (code "51") (name "PH") (class "Default")
      (node (ref "U2") (pin "P$21") (pinfunction "PH_P$21") (pintype "bidirectional"))
      (node (ref "U2") (pin "P$22") (pinfunction "PH_P$22") (pintype "bidirectional"))
      (node (ref "U2") (pin "P$23") (pinfunction "PH_P$23") (pintype "bidirectional"))
      (node (ref "U2") (pin "P$24") (pinfunction "PH_P$24") (pintype "bidirectional"))
      (node (ref "U2") (pin "P$6") (pinfunction "PH_P$6") (pintype "bidirectional"))
      (node (ref "U2") (pin "P$7") (pinfunction "PH_P$7") (pintype "bidirectional"))
      (node (ref "U2") (pin "PH1") (pinfunction "PH_PH1") (pintype "bidirectional"))
      (node (ref "U2") (pin "PH2") (pinfunction "PH_PH2") (pintype "bidirectional"))
    )
    (net (code "52") (name "PWM_5V") (class "Default")
      (node (ref "J12") (pin "2") (pinfunction "3_2") (pintype "passive"))
    )
    (net (code "53") (name "RB_OUT") (class "Default")
      (node (ref "J8") (pin "1") (pinfunction "1_1") (pintype "passive"))
      (node (ref "Q3") (pin "4") (pinfunction "D_4") (pintype "passive"))
    )
    (net (code "54") (name "RB_PWM") (class "Default")
      (node (ref "R7") (pin "2") (pinfunction "2_2") (pintype "passive"))
      (node (ref "U1") (pin "23") (pinfunction "PA14(XIN/SER2:2+)_23") (pintype "bidirectional"))
    )
    (net (code "55") (name "RG_OUT") (class "Default")
      (node (ref "J8") (pin "3") (pinfunction "3_3") (pintype "passive"))
      (node (ref "Q4") (pin "4") (pinfunction "D_4") (pintype "passive"))
    )
    (net (code "56") (name "RG_PWM") (class "Default")
      (node (ref "R5") (pin "2") (pinfunction "2_2") (pintype "passive"))
      (node (ref "U1") (pin "16") (pinfunction "PA11(AIN19/SER0:3+)_16") (pintype "bidirectional"))
    )
    (net (code "57") (name "RR_OUT") (class "Default")
      (node (ref "J8") (pin "2") (pinfunction "2_2") (pintype "passive"))
      (node (ref "Q3") (pin "6") (pinfunction "D_6") (pintype "passive"))
    )
    (net (code "58") (name "RR_PWM") (class "Default")
      (node (ref "R6") (pin "2") (pinfunction "2_2") (pintype "passive"))
      (node (ref "U1") (pin "15") (pinfunction "PA10(AIN18/SER0:2+)_15") (pintype "bidirectional"))
    )
    (net (code "59") (name "SCL") (class "Default")
      (node (ref "R16") (pin "2") (pinfunction "2_2") (pintype "passive"))
      (node (ref "TP5") (pin "P$1") (pinfunction "1_P$1") (pintype "bidirectional"))
      (node (ref "U1") (pin "32") (pinfunction "PA23(I2C/SER3:0+)_32") (pintype "bidirectional"))
      (node (ref "U7") (pin "13") (pinfunction "SCL_13") (pintype "bidirectional"))
    )
    (net (code "60") (name "SDA") (class "Default")
      (node (ref "R15") (pin "2") (pinfunction "2_2") (pintype "passive"))
      (node (ref "TP4") (pin "P$1") (pinfunction "1_P$1") (pintype "bidirectional"))
      (node (ref "U1") (pin "31") (pinfunction "PA22(I2C/SER3:0+)_31") (pintype "bidirectional"))
      (node (ref "U7") (pin "14") (pinfunction "SDA_14") (pintype "bidirectional"))
    )
    (net (code "61") (name "STATUS_LED") (class "Default")
      (node (ref "R36") (pin "2") (pinfunction "2_2") (pintype "passive"))
      (node (ref "U1") (pin "48") (pinfunction "PB03(AIN11/SER5:1)_48") (pintype "bidirectional"))
    )
    (net (code "62") (name "SWCLK") (class "Default")
      (node (ref "J5") (pin "4") (pinfunction "SWDCLK/TCK_4") (pintype "bidirectional"))
      (node (ref "TP9") (pin "P$1") (pinfunction "1_P$1") (pintype "bidirectional"))
      (node (ref "U1") (pin "45") (pinfunction "PA30(SWCLK/SER1:2+)_45") (pintype "bidirectional"))
    )
    (net (code "63") (name "SWDIO") (class "Default")
      (node (ref "J5") (pin "2") (pinfunction "SWDIO/TMS_2") (pintype "bidirectional"))
      (node (ref "TP8") (pin "P$1") (pinfunction "1_P$1") (pintype "bidirectional"))
      (node (ref "U1") (pin "46") (pinfunction "PA31(SWDIO/SER1:3+)_46") (pintype "bidirectional"))
    )
    (net (code "64") (name "TAIL_OUT") (class "Default")
      (node (ref "J7") (pin "1") (pinfunction "1_1") (pintype "passive"))
      (node (ref "Q4") (pin "6") (pinfunction "D_6") (pintype "passive"))
    )
    (net (code "65") (name "TAIL_PWM") (class "Default")
      (node (ref "R8") (pin "2") (pinfunction "2_2") (pintype "passive"))
      (node (ref "U1") (pin "21") (pinfunction "PA12(I2C/SER2:0+)_21") (pintype "bidirectional"))
    )
    (net (code "66") (name "USB_D+") (class "Default")
      (node (ref "J1") (pin "3") (pinfunction "D+_3") (pintype "bidirectional"))
      (node (ref "U1") (pin "34") (pinfunction "PA25(SER3:3+)_34") (pintype "bidirectional"))
    )
    (net (code "67") (name "USB_D-") (class "Default")
      (node (ref "J1") (pin "2") (pinfunction "D-_2") (pintype "bidirectional"))
      (node (ref "U1") (pin "33") (pinfunction "PA24(SER3:2+)_33") (pintype "bidirectional"))
    )
    (net (code "68") (name "VCC") (class "Default")
      (node (ref "D2") (pin "ANODE") (pinfunction "ANODE_ANODE") (pintype "bidirectional"))
    )
    (net (code "69") (name "VUSB") (class "Default")
      (node (ref "J1") (pin "1") (pinfunction "VBUS_1") (pintype "power_in"))
      (node (ref "R23") (pin "1") (pinfunction "1_1") (pintype "passive"))
    )
    (net (code "70") (name "unconnected-(J1-ID-Pad4)") (class "Default")
      (node (ref "J1") (pin "4") (pinfunction "ID_4") (pintype "passive"))
    )
    (net (code "71") (name "unconnected-(J5-GNDDTCT-Pad9)") (class "Default")
      (node (ref "J5") (pin "9") (pinfunction "GNDDTCT_9") (pintype "bidirectional"))
    )
    (net (code "72") (name "unconnected-(J5-KEY-Pad7)") (class "Default")
      (node (ref "J5") (pin "7") (pinfunction "KEY_7") (pintype "bidirectional"))
    )
    (net (code "73") (name "unconnected-(J5-NC{slash}TDI-Pad8)") (class "Default")
      (node (ref "J5") (pin "8") (pinfunction "NC/TDI_8") (pintype "bidirectional"))
    )
    (net (code "74") (name "unconnected-(J5-SWO{slash}TDO-Pad6)") (class "Default")
      (node (ref "J5") (pin "6") (pinfunction "SWO/TDO_6") (pintype "bidirectional"))
    )
    (net (code "75") (name "unconnected-(U1-PA02(AIN0{slash}DAC)-Pad3)") (class "Default")
      (node (ref "U1") (pin "3") (pinfunction "PA02(AIN0/DAC)_3") (pintype "bidirectional"))
    )
    (net (code "76") (name "unconnected-(U1-PA03(AIN1{slash}REFA)-Pad4)") (class "Default")
      (node (ref "U1") (pin "4") (pinfunction "PA03(AIN1/REFA)_4") (pintype "bidirectional"))
    )
    (net (code "77") (name "unconnected-(U1-PA04(AIN4{slash}REFB{slash}SER0:0{slash}TC0:0)-Pad9)") (class "Default")
      (node (ref "U1") (pin "9") (pinfunction "PA04(AIN4/REFB/SER0:0/TC0:0)_9") (pintype "bidirectional"))
    )
    (net (code "78") (name "unconnected-(U1-PA05(AIN5{slash}SER0:1{slash}TC0:1)-Pad10)") (class "Default")
      (node (ref "U1") (pin "10") (pinfunction "PA05(AIN5/SER0:1/TC0:1)_10") (pintype "bidirectional"))
    )
    (net (code "79") (name "unconnected-(U1-PA17(I2C{slash}SER1:1+)-Pad26)") (class "Default")
      (node (ref "U1") (pin "26") (pinfunction "PA17(I2C/SER1:1+)_26") (pintype "bidirectional"))
    )
    (net (code "80") (name "unconnected-(U1-PA19(SER1:3+)-Pad28)") (class "Default")
      (node (ref "U1") (pin "28") (pinfunction "PA19(SER1:3+)_28") (pintype "bidirectional"))
    )
    (net (code "81") (name "unconnected-(U1-PA27-Pad39)") (class "Default")
      (node (ref "U1") (pin "39") (pinfunction "PA27_39") (pintype "bidirectional"))
    )
    (net (code "82") (name "unconnected-(U1-PA28-Pad41)") (class "Default")
      (node (ref "U1") (pin "41") (pinfunction "PA28_41") (pintype "bidirectional"))
    )
    (net (code "83") (name "unconnected-(U1-PB08(AIN2{slash}SER4:0{slash}TC4:0)-Pad7)") (class "Default")
      (node (ref "U1") (pin "7") (pinfunction "PB08(AIN2/SER4:0/TC4:0)_7") (pintype "bidirectional"))
    )
    (net (code "84") (name "unconnected-(U1-PB09(AIN3{slash}SER4:1{slash}TC4:1)-Pad8)") (class "Default")
      (node (ref "U1") (pin "8") (pinfunction "PB09(AIN3/SER4:1/TC4:1)_8") (pintype "bidirectional"))
    )
    (net (code "85") (name "unconnected-(U1-PB10(SER4:2+)-Pad19)") (class "Default")
      (node (ref "U1") (pin "19") (pinfunction "PB10(SER4:2+)_19") (pintype "bidirectional"))
    )
    (net (code "86") (name "unconnected-(U1-PB22(SER5:2+)-Pad37)") (class "Default")
      (node (ref "U1") (pin "37") (pinfunction "PB22(SER5:2+)_37") (pintype "bidirectional"))
    )
    (net (code "87") (name "unconnected-(U1-PB23(SER5:3+)-Pad38)") (class "Default")
      (node (ref "U1") (pin "38") (pinfunction "PB23(SER5:3+)_38") (pintype "bidirectional"))
    )
    (net (code "88") (name "unconnected-(U2-PWRGD-PadP$35)") (class "Default")
      (node (ref "U2") (pin "P$35") (pinfunction "PWRGD_P$35") (pintype "bidirectional"))
    )
    (net (code "89") (name "unconnected-(U3-NC-PadNC@5)") (class "Default")
      (node (ref "U3") (pin "NC@5") (pinfunction "NC_NC@5") (pintype "bidirectional"))
    )
    (net (code "90") (name "unconnected-(U3-NC-PadNC@6)") (class "Default")
      (node (ref "U3") (pin "NC@6") (pinfunction "NC_NC@6") (pintype "bidirectional"))
    )
    (net (code "91") (name "unconnected-(U3-NC-PadNC@7)") (class "Default")
      (node (ref "U3") (pin "NC@7") (pinfunction "NC_NC@7") (pintype "bidirectional"))
    )
    (net (code "92") (name "unconnected-(U3-NC-PadNC@8)") (class "Default")
      (node (ref "U3") (pin "NC@8") (pinfunction "NC_NC@8") (pintype "bidirectional"))
    )
    (net (code "93") (name "unconnected-(U3-NC-PadNC@10)") (class "Default")
      (node (ref "U3") (pin "NC@10") (pinfunction "NC_NC@10") (pintype "bidirectional"))
    )
    (net (code "94") (name "unconnected-(U3-PadPIO0)") (class "Default")
      (node (ref "U3") (pin "PIO0") (pinfunction "PIO0_PIO0") (pintype "bidirectional"))
    )
    (net (code "95") (name "unconnected-(U3-PadPIO1)") (class "Default")
      (node (ref "U3") (pin "PIO1") (pinfunction "PIO1_PIO1") (pintype "bidirectional"))
    )
    (net (code "96") (name "unconnected-(U3-PadPIO2)") (class "Default")
      (node (ref "U3") (pin "PIO2") (pinfunction "PIO2_PIO2") (pintype "bidirectional"))
    )
    (net (code "97") (name "unconnected-(U3-PadPIO3)") (class "Default")
      (node (ref "U3") (pin "PIO3") (pinfunction "PIO3_PIO3") (pintype "bidirectional"))
    )
    (net (code "98") (name "unconnected-(U3-PadRESETB)") (class "Default")
      (node (ref "U3") (pin "RESETB") (pinfunction "RESETB_RESETB") (pintype "bidirectional"))
    )
    (net (code "99") (name "unconnected-(U3-PadUART_CTS)") (class "Default")
      (node (ref "U3") (pin "UART_CTS") (pinfunction "UART_CTS_UART_CTS") (pintype "bidirectional"))
    )
    (net (code "100") (name "unconnected-(U3-PadUART_RTS)") (class "Default")
      (node (ref "U3") (pin "UART_RTS") (pinfunction "UART_RTS_UART_RTS") (pintype "bidirectional"))
    )
    (net (code "101") (name "unconnected-(U7-INT1-Pad4)") (class "Default")
      (node (ref "U7") (pin "4") (pinfunction "INT1_4") (pintype "bidirectional"))
    )
    (net (code "102") (name "unconnected-(U7-INT2-Pad9)") (class "Default")
      (node (ref "U7") (pin "9") (pinfunction "INT2_9") (pintype "bidirectional"))
    )
    (net (code "103") (name "unconnected-(U7-NC-Pad11)") (class "Default")
      (node (ref "U7") (pin "11") (pinfunction "NC_11") (pintype "bidirectional"))
    )
    (net (code "104") (name "unconnected-(U7-OCS-Pad10)") (class "Default")
      (node (ref "U7") (pin "10") (pinfunction "OCS_10") (pintype "bidirectional"))
    )
  )
)
